# IO.net
KiCad netlist of a schematic drawn in Altium Designer
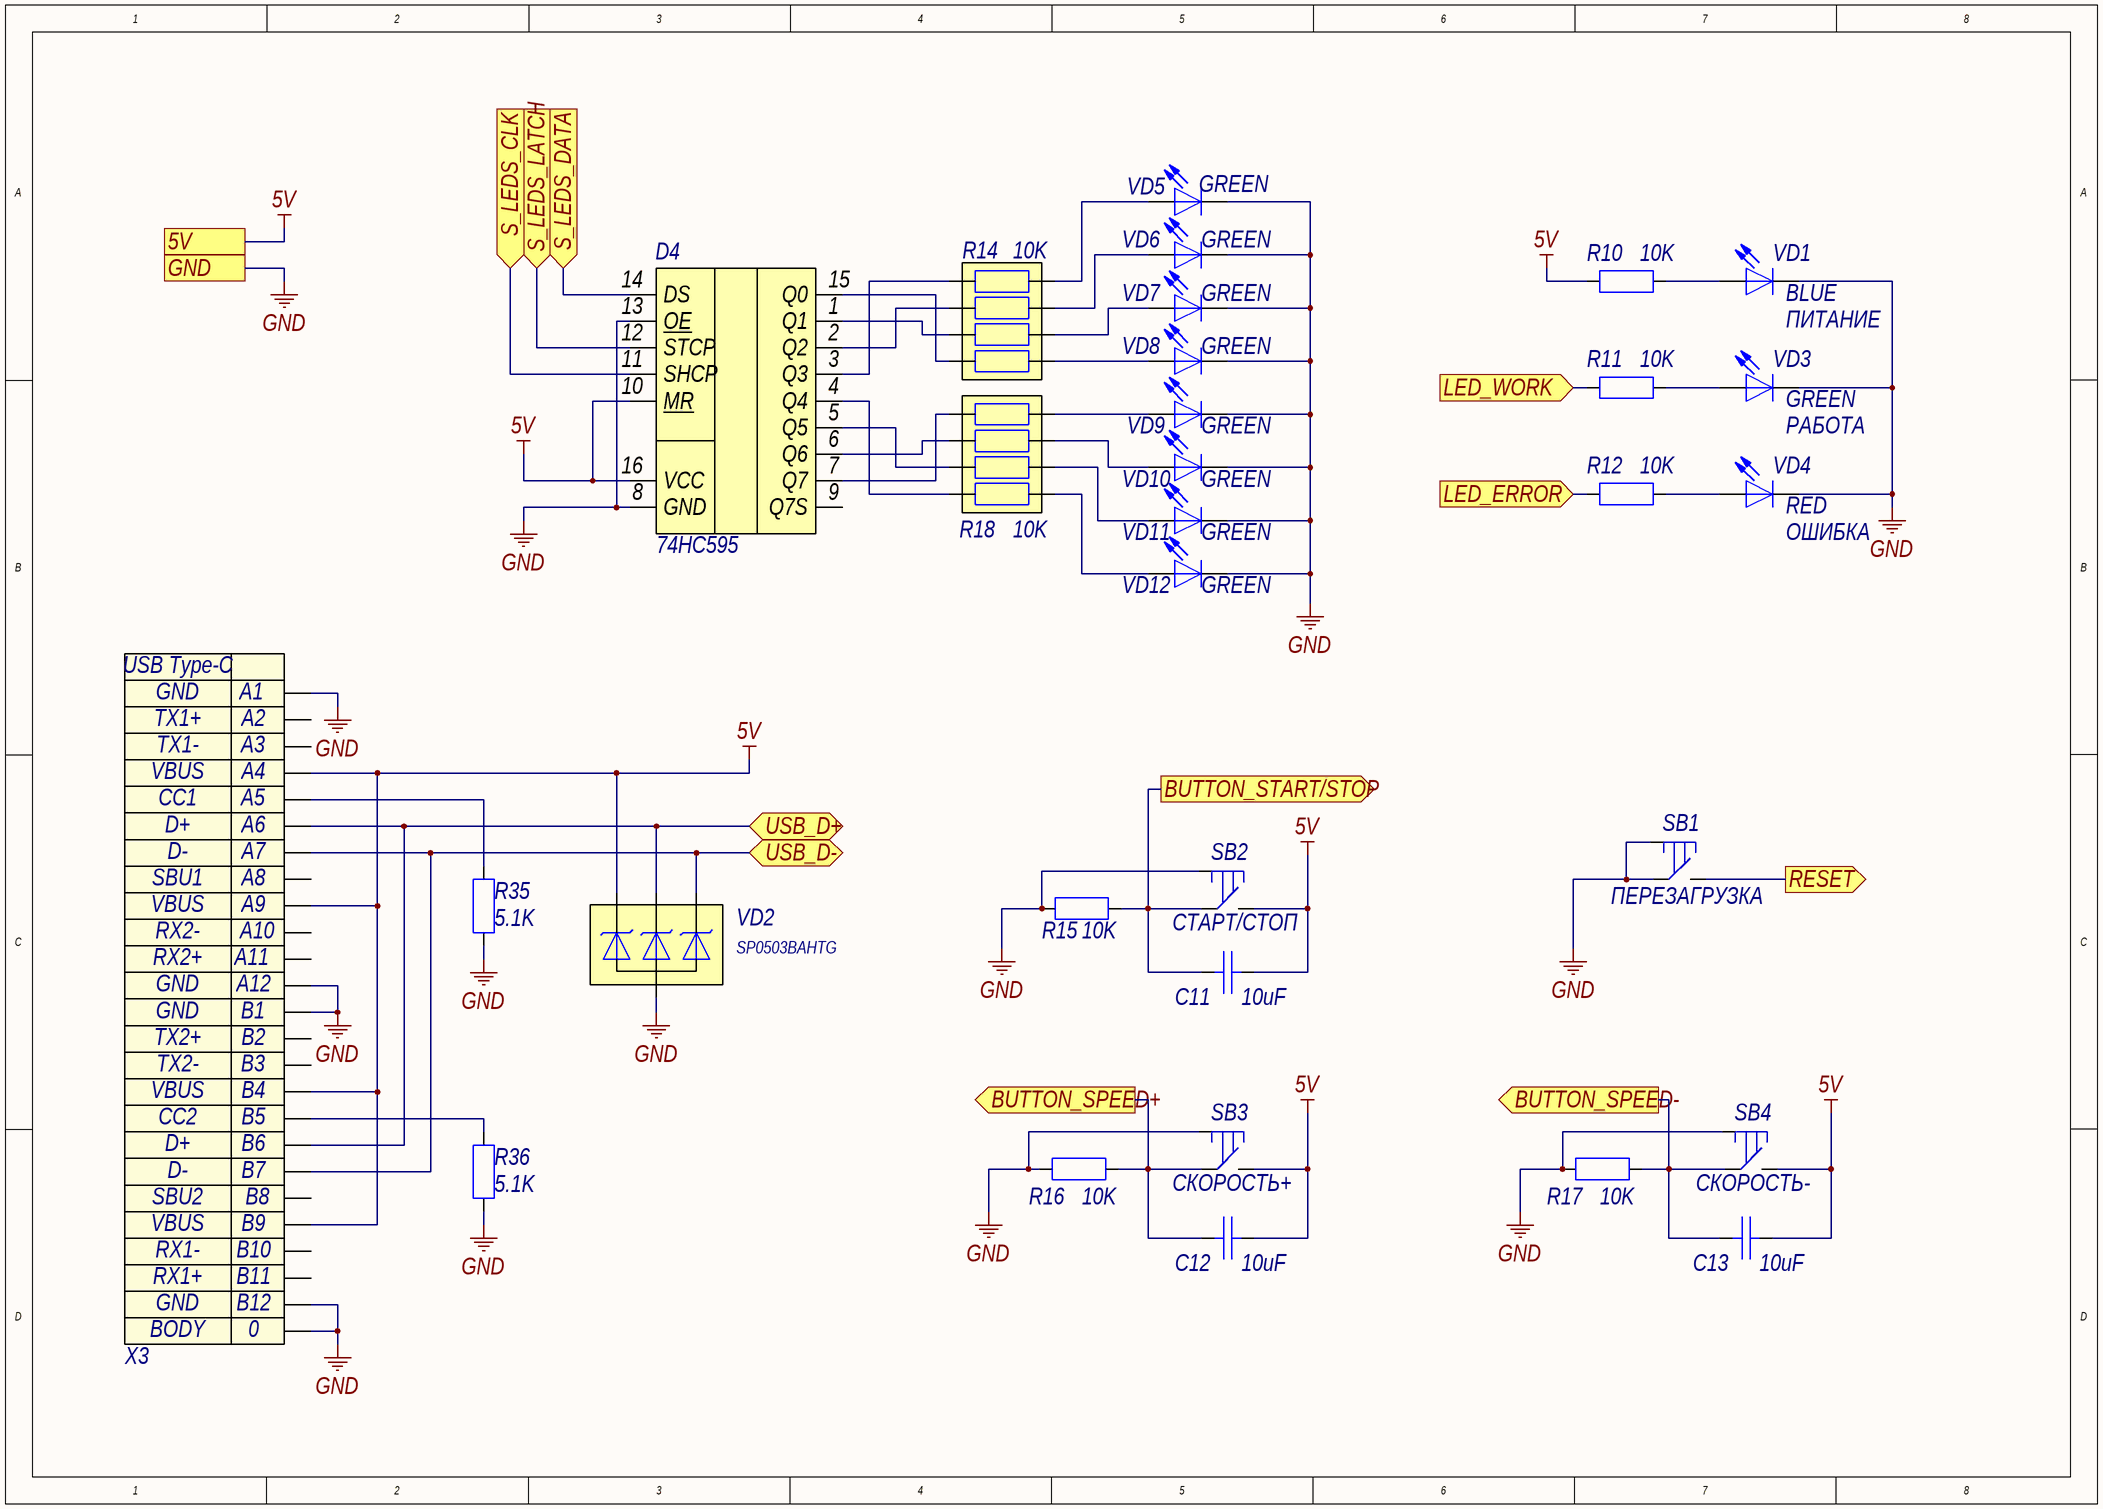
[diagram p0: IO.SchDoc]

(export (version "E")
  (design (tool "Eeschema 10.0.6"))
  (components
    (comp (ref "C11")
      (value "10uF")
      (footprint "Footprints:NPC0805")
      (description "Nonpolarized Capacitor (Ceramic)")
      (libsource (lib "Passive") (part "Nonpolarized Capacitor"))
    )
    (comp (ref "C12")
      (value "10uF")
      (footprint "Footprints:NPC0805")
      (description "Nonpolarized Capacitor (Ceramic)")
      (libsource (lib "Passive") (part "Nonpolarized Capacitor"))
    )
    (comp (ref "C13")
      (value "10uF")
      (footprint "Footprints:NPC0805")
      (description "Nonpolarized Capacitor (Ceramic)")
      (libsource (lib "Passive") (part "Nonpolarized Capacitor"))
    )
    (comp (ref "D4")
      (value "74HC595")
      (footprint "SOIC16")
      (description "Сдвиговый регистр, 8 каналов")
      (libsource (lib "Miscellaneous") (part "74HC595"))
    )
    (comp (ref "R10")
      (value "10K")
      (footprint "Footprints:R0805")
      (description "Resistor")
      (libsource (lib "") (part "Resistor_1"))
    )
    (comp (ref "R11")
      (value "10K")
      (footprint "Footprints:R0805")
      (description "Resistor")
      (libsource (lib "") (part "Resistor_1"))
    )
    (comp (ref "R12")
      (value "10K")
      (footprint "Footprints:R0805")
      (description "Resistor")
      (libsource (lib "") (part "Resistor_1"))
    )
    (comp (ref "R14")
      (value "10K")
      (footprint "Footprints:CAT16")
      (description "Resistor Array")
      (libsource (lib "Passive") (part "Resistor Array"))
    )
    (comp (ref "R15")
      (value "10K")
      (footprint "Footprints:R0805")
      (description "Resistor")
      (libsource (lib "") (part "Resistor_1"))
    )
    (comp (ref "R16")
      (value "10K")
      (footprint "Footprints:R0805")
      (description "Resistor")
      (libsource (lib "") (part "Resistor_1"))
    )
    (comp (ref "R17")
      (value "10K")
      (footprint "Footprints:R0805")
      (description "Resistor")
      (libsource (lib "") (part "Resistor_1"))
    )
    (comp (ref "R18")
      (value "10K")
      (footprint "Footprints:CAT16")
      (description "Resistor Array")
      (libsource (lib "Passive") (part "Resistor Array"))
    )
    (comp (ref "R35")
      (value "5.1K")
      (footprint "Footprints:R0805")
      (description "Resistor")
      (libsource (lib "Passive") (part "Resistor"))
    )
    (comp (ref "R36")
      (value "5.1K")
      (footprint "Footprints:R0805")
      (description "Resistor")
      (libsource (lib "Passive") (part "Resistor"))
    )
    (comp (ref "SB1")
      (value "~")
      (footprint "1-1437565-6 WITH LABEL")
      (description "Кнопка без фиксации")
      (fields (field (name "FUNCTION") "ПЕРЕЗАГРУЗКА"))
      (libsource (lib "LibSCH") (part "Button_SMD"))
    )
    (comp (ref "SB2")
      (value "~")
      (footprint "1-1437565-6 WITH LABEL")
      (description "Кнопка без фиксации")
      (fields (field (name "FUNCTION") "СТАРТ/СТОП"))
      (libsource (lib "LibSCH") (part "Button_SMD"))
    )
    (comp (ref "SB3")
      (value "~")
      (footprint "1-1437565-6 WITH LABEL")
      (description "Кнопка без фиксации")
      (fields (field (name "FUNCTION") "СКОРОСТЬ+"))
      (libsource (lib "LibSCH") (part "Button_SMD"))
    )
    (comp (ref "SB4")
      (value "~")
      (footprint "1-1437565-6 WITH LABEL")
      (description "Кнопка без фиксации")
      (fields (field (name "FUNCTION") "СКОРОСТЬ-"))
      (libsource (lib "LibSCH") (part "Button_SMD"))
    )
    (comp (ref "VD1")
      (value "~")
      (footprint "0805_LED _BLUE")
      (description "Светодиод SMD")
      (fields
        (field (name "NAME") "ПИТАНИЕ")
        (field (name "MANUFACTURER") "KGB")
        (field (name "COLOR") "BLUE")
      )
      (libsource (lib "Diodes") (part "LED"))
    )
    (comp (ref "VD2")
      (value "SP0503BAHTG")
      (footprint "Footprints:SOT143")
      (description "3 TVS Diodes assembly, 5V")
      (libsource (lib "Diodes") (part "SP0503BAHTG"))
    )
    (comp (ref "VD3")
      (value "~")
      (footprint "0805_LED _GREEN")
      (description "Светодиод SMD")
      (fields
        (field (name "NAME") "РАБОТА")
        (field (name "MANUFACTURER") "KGB")
        (field (name "COLOR") "GREEN")
      )
      (libsource (lib "Diodes") (part "LED"))
    )
    (comp (ref "VD4")
      (value "~")
      (footprint "0805_LED _RED")
      (description "Светодиод SMD")
      (fields (field (name "NAME") "ОШИБКА") (field (name "MANUFACTURER") "KGB") (field (name "COLOR") "RED"))
      (libsource (lib "Diodes") (part "LED"))
    )
    (comp (ref "VD5")
      (value "GREEN")
      (footprint "0805_LED _GREEN")
      (description "Светодиод SMD")
      (fields (field (name "MANUFACTURER") "KGB"))
      (libsource (lib "Diodes") (part "LED"))
    )
    (comp (ref "VD6")
      (value "~")
      (footprint "0805_LED _GREEN")
      (description "Светодиод SMD")
      (fields (field (name "MANUFACTURER") "KGB") (field (name "COLOR") "GREEN"))
      (libsource (lib "Diodes") (part "LED"))
    )
    (comp (ref "VD7")
      (value "~")
      (footprint "0805_LED _GREEN")
      (description "Светодиод SMD")
      (fields (field (name "MANUFACTURER") "KGB") (field (name "COLOR") "GREEN"))
      (libsource (lib "Diodes") (part "LED"))
    )
    (comp (ref "VD8")
      (value "~")
      (footprint "0805_LED _GREEN")
      (description "Светодиод SMD")
      (fields (field (name "MANUFACTURER") "KGB") (field (name "COLOR") "GREEN"))
      (libsource (lib "Diodes") (part "LED"))
    )
    (comp (ref "VD9")
      (value "~")
      (footprint "0805_LED _GREEN")
      (description "Светодиод SMD")
      (fields (field (name "MANUFACTURER") "KGB") (field (name "COLOR") "GREEN"))
      (libsource (lib "Diodes") (part "LED"))
    )
    (comp (ref "VD10")
      (value "~")
      (footprint "0805_LED _GREEN")
      (description "Светодиод SMD")
      (fields (field (name "MANUFACTURER") "KGB") (field (name "COLOR") "GREEN"))
      (libsource (lib "Diodes") (part "LED"))
    )
    (comp (ref "VD11")
      (value "~")
      (footprint "0805_LED _GREEN")
      (description "Светодиод SMD")
      (fields (field (name "MANUFACTURER") "KGB") (field (name "COLOR") "GREEN"))
      (libsource (lib "Diodes") (part "LED"))
    )
    (comp (ref "VD12")
      (value "~")
      (footprint "0805_LED _GREEN")
      (description "Светодиод SMD")
      (fields (field (name "MANUFACTURER") "KGB") (field (name "COLOR") "GREEN"))
      (libsource (lib "Diodes") (part "LED"))
    )
    (comp (ref "X3")
      (value "USB Type-C")
      (footprint "Footprints:USB Type-C Vertical")
      (description "USB Type-C connector")
      (libsource (lib "Mechanical") (part "USB Type-C"))
    )
  )
  (nets
    (net (code "1") (name "/BUTTON_SPEED+") (class "Default")
      (node (ref "C12") (pin "1") (pinfunction "1_1") (pintype "passive"))
      (node (ref "R16") (pin "2") (pinfunction "2_2") (pintype "passive"))
      (node (ref "SB3") (pin "1") (pinfunction "1_1") (pintype "passive"))
    )
    (net (code "2") (name "/BUTTON_SPEED-") (class "Default")
      (node (ref "C13") (pin "1") (pinfunction "1_1") (pintype "passive"))
      (node (ref "R17") (pin "2") (pinfunction "2_2") (pintype "passive"))
      (node (ref "SB4") (pin "1") (pinfunction "1_1") (pintype "passive"))
    )
    (net (code "3") (name "/BUTTON_START{slash}STOP") (class "Default")
      (node (ref "C11") (pin "1") (pinfunction "1_1") (pintype "passive"))
      (node (ref "R15") (pin "2") (pinfunction "2_2") (pintype "passive"))
      (node (ref "SB2") (pin "1") (pinfunction "1_1") (pintype "passive"))
    )
    (net (code "4") (name "/LED_ERROR") (class "Default")
      (node (ref "R12") (pin "1") (pinfunction "1_1") (pintype "passive"))
    )
    (net (code "5") (name "/LED_WORK") (class "Default")
      (node (ref "R11") (pin "1") (pinfunction "1_1") (pintype "passive"))
    )
    (net (code "6") (name "/RESET") (class "Default")
      (node (ref "SB1") (pin "2") (pinfunction "2_2") (pintype "passive"))
    )
    (net (code "7") (name "/S_LEDS_CLK") (class "Default")
      (node (ref "D4") (pin "11") (pinfunction "SHCP_11") (pintype "passive"))
    )
    (net (code "8") (name "/S_LEDS_DATA") (class "Default")
      (node (ref "D4") (pin "14") (pinfunction "DS_14") (pintype "passive"))
    )
    (net (code "9") (name "/S_LEDS_LATCH") (class "Default")
      (node (ref "D4") (pin "12") (pinfunction "STCP_12") (pintype "passive"))
    )
    (net (code "10") (name "/USB_D+") (class "Default")
      (node (ref "VD2") (pin "3") (pinfunction "C_3") (pintype "passive"))
      (node (ref "X3") (pin "A6") (pintype "passive"))
      (node (ref "X3") (pin "B6") (pintype "passive"))
    )
    (net (code "11") (name "/USB_D-") (class "Default")
      (node (ref "VD2") (pin "4") (pinfunction "C_4") (pintype "passive"))
      (node (ref "X3") (pin "A7") (pintype "passive"))
      (node (ref "X3") (pin "B7") (pintype "passive"))
    )
    (net (code "12") (name "5V") (class "Default")
      (node (ref "C11") (pin "2") (pinfunction "2_2") (pintype "passive"))
      (node (ref "C12") (pin "2") (pinfunction "2_2") (pintype "passive"))
      (node (ref "C13") (pin "2") (pinfunction "2_2") (pintype "passive"))
      (node (ref "D4") (pin "10") (pinfunction "MR_10") (pintype "passive"))
      (node (ref "D4") (pin "16") (pinfunction "VCC_16") (pintype "passive"))
      (node (ref "R10") (pin "1") (pinfunction "1_1") (pintype "passive"))
      (node (ref "SB2") (pin "2") (pinfunction "2_2") (pintype "passive"))
      (node (ref "SB3") (pin "2") (pinfunction "2_2") (pintype "passive"))
      (node (ref "SB4") (pin "2") (pinfunction "2_2") (pintype "passive"))
      (node (ref "VD2") (pin "2") (pinfunction "C_2") (pintype "passive"))
      (node (ref "X3") (pin "A4") (pintype "passive"))
      (node (ref "X3") (pin "A9") (pintype "passive"))
      (node (ref "X3") (pin "B4") (pintype "passive"))
      (node (ref "X3") (pin "B9") (pintype "passive"))
    )
    (net (code "13") (name "GND") (class "Default")
      (node (ref "D4") (pin "13") (pinfunction "OE_13") (pintype "passive"))
      (node (ref "D4") (pin "8") (pinfunction "GND_8") (pintype "passive"))
      (node (ref "R15") (pin "1") (pinfunction "1_1") (pintype "passive"))
      (node (ref "R16") (pin "1") (pinfunction "1_1") (pintype "passive"))
      (node (ref "R17") (pin "1") (pinfunction "1_1") (pintype "passive"))
      (node (ref "R35") (pin "1") (pinfunction "1_1") (pintype "passive"))
      (node (ref "R36") (pin "1") (pinfunction "1_1") (pintype "passive"))
      (node (ref "SB1") (pin "1") (pinfunction "1_1") (pintype "passive"))
      (node (ref "SB1") (pin "3") (pinfunction "GND_3") (pintype "passive"))
      (node (ref "SB2") (pin "3") (pinfunction "GND_3") (pintype "passive"))
      (node (ref "SB3") (pin "3") (pinfunction "GND_3") (pintype "passive"))
      (node (ref "SB4") (pin "3") (pinfunction "GND_3") (pintype "passive"))
      (node (ref "VD1") (pin "1") (pinfunction "K_1") (pintype "passive"))
      (node (ref "VD10") (pin "1") (pinfunction "K_1") (pintype "passive"))
      (node (ref "VD11") (pin "1") (pinfunction "K_1") (pintype "passive"))
      (node (ref "VD12") (pin "1") (pinfunction "K_1") (pintype "passive"))
      (node (ref "VD2") (pin "1") (pinfunction "A_1") (pintype "passive"))
      (node (ref "VD3") (pin "1") (pinfunction "K_1") (pintype "passive"))
      (node (ref "VD4") (pin "1") (pinfunction "K_1") (pintype "passive"))
      (node (ref "VD5") (pin "1") (pinfunction "K_1") (pintype "passive"))
      (node (ref "VD6") (pin "1") (pinfunction "K_1") (pintype "passive"))
      (node (ref "VD7") (pin "1") (pinfunction "K_1") (pintype "passive"))
      (node (ref "VD8") (pin "1") (pinfunction "K_1") (pintype "passive"))
      (node (ref "VD9") (pin "1") (pinfunction "K_1") (pintype "passive"))
      (node (ref "X3") (pin "0") (pintype "passive"))
      (node (ref "X3") (pin "A1") (pintype "passive"))
      (node (ref "X3") (pin "A12") (pintype "passive"))
      (node (ref "X3") (pin "B1") (pintype "passive"))
      (node (ref "X3") (pin "B12") (pintype "passive"))
    )
    (net (code "14") (name "Net-(D4-Q0)") (class "Default")
      (node (ref "D4") (pin "15") (pinfunction "Q0_15") (pintype "passive"))
      (node (ref "R14") (pin "4") (pinfunction "4_4") (pintype "passive"))
    )
    (net (code "15") (name "Net-(D4-Q1)") (class "Default")
      (node (ref "D4") (pin "1") (pinfunction "Q1_1") (pintype "passive"))
      (node (ref "R14") (pin "3") (pinfunction "3_3") (pintype "passive"))
    )
    (net (code "16") (name "Net-(D4-Q2)") (class "Default")
      (node (ref "D4") (pin "2") (pinfunction "Q2_2") (pintype "passive"))
      (node (ref "R14") (pin "2") (pinfunction "2_2") (pintype "passive"))
    )
    (net (code "17") (name "Net-(D4-Q3)") (class "Default")
      (node (ref "D4") (pin "3") (pinfunction "Q3_3") (pintype "passive"))
      (node (ref "R14") (pin "1") (pinfunction "1_1") (pintype "passive"))
    )
    (net (code "18") (name "Net-(D4-Q4)") (class "Default")
      (node (ref "D4") (pin "4") (pinfunction "Q4_4") (pintype "passive"))
      (node (ref "R18") (pin "4") (pinfunction "4_4") (pintype "passive"))
    )
    (net (code "19") (name "Net-(D4-Q5)") (class "Default")
      (node (ref "D4") (pin "5") (pinfunction "Q5_5") (pintype "passive"))
      (node (ref "R18") (pin "3") (pinfunction "3_3") (pintype "passive"))
    )
    (net (code "20") (name "Net-(D4-Q6)") (class "Default")
      (node (ref "D4") (pin "6") (pinfunction "Q6_6") (pintype "passive"))
      (node (ref "R18") (pin "2") (pinfunction "2_2") (pintype "passive"))
    )
    (net (code "21") (name "Net-(D4-Q7)") (class "Default")
      (node (ref "D4") (pin "7") (pinfunction "Q7_7") (pintype "passive"))
      (node (ref "R18") (pin "1") (pinfunction "1_1") (pintype "passive"))
    )
    (net (code "22") (name "Net-(R35-Pad2)") (class "Default")
      (node (ref "R35") (pin "2") (pinfunction "2_2") (pintype "passive"))
      (node (ref "X3") (pin "A5") (pintype "passive"))
    )
    (net (code "23") (name "Net-(R36-Pad2)") (class "Default")
      (node (ref "R36") (pin "2") (pinfunction "2_2") (pintype "passive"))
      (node (ref "X3") (pin "B5") (pintype "passive"))
    )
    (net (code "24") (name "Net-(VD1-A)") (class "Default")
      (node (ref "R10") (pin "2") (pinfunction "2_2") (pintype "passive"))
      (node (ref "VD1") (pin "2") (pinfunction "A_2") (pintype "passive"))
    )
    (net (code "25") (name "Net-(VD3-A)") (class "Default")
      (node (ref "R11") (pin "2") (pinfunction "2_2") (pintype "passive"))
      (node (ref "VD3") (pin "2") (pinfunction "A_2") (pintype "passive"))
    )
    (net (code "26") (name "Net-(VD4-A)") (class "Default")
      (node (ref "R12") (pin "2") (pinfunction "2_2") (pintype "passive"))
      (node (ref "VD4") (pin "2") (pinfunction "A_2") (pintype "passive"))
    )
    (net (code "27") (name "Net-(VD5-A)") (class "Default")
      (node (ref "R14") (pin "8") (pinfunction "8_8") (pintype "passive"))
      (node (ref "VD5") (pin "2") (pinfunction "A_2") (pintype "passive"))
    )
    (net (code "28") (name "Net-(VD6-A)") (class "Default")
      (node (ref "R14") (pin "7") (pinfunction "7_7") (pintype "passive"))
      (node (ref "VD6") (pin "2") (pinfunction "A_2") (pintype "passive"))
    )
    (net (code "29") (name "Net-(VD7-A)") (class "Default")
      (node (ref "R14") (pin "6") (pinfunction "6_6") (pintype "passive"))
      (node (ref "VD7") (pin "2") (pinfunction "A_2") (pintype "passive"))
    )
    (net (code "30") (name "Net-(VD8-A)") (class "Default")
      (node (ref "R14") (pin "5") (pinfunction "5_5") (pintype "passive"))
      (node (ref "VD8") (pin "2") (pinfunction "A_2") (pintype "passive"))
    )
    (net (code "31") (name "Net-(VD9-A)") (class "Default")
      (node (ref "R18") (pin "8") (pinfunction "8_8") (pintype "passive"))
      (node (ref "VD9") (pin "2") (pinfunction "A_2") (pintype "passive"))
    )
    (net (code "32") (name "Net-(VD10-A)") (class "Default")
      (node (ref "R18") (pin "7") (pinfunction "7_7") (pintype "passive"))
      (node (ref "VD10") (pin "2") (pinfunction "A_2") (pintype "passive"))
    )
    (net (code "33") (name "Net-(VD11-A)") (class "Default")
      (node (ref "R18") (pin "6") (pinfunction "6_6") (pintype "passive"))
      (node (ref "VD11") (pin "2") (pinfunction "A_2") (pintype "passive"))
    )
    (net (code "34") (name "Net-(VD12-A)") (class "Default")
      (node (ref "R18") (pin "5") (pinfunction "5_5") (pintype "passive"))
      (node (ref "VD12") (pin "2") (pinfunction "A_2") (pintype "passive"))
    )
    (net (code "35") (name "unconnected-(D4-Q7S-Pad9)") (class "Default")
      (node (ref "D4") (pin "9") (pinfunction "Q7S_9") (pintype "passive"))
    )
    (net (code "36") (name "unconnected-(X3-PadA2)") (class "Default")
      (node (ref "X3") (pin "A2") (pintype "passive"))
    )
    (net (code "37") (name "unconnected-(X3-PadA3)") (class "Default")
      (node (ref "X3") (pin "A3") (pintype "passive"))
    )
    (net (code "38") (name "unconnected-(X3-PadA8)") (class "Default")
      (node (ref "X3") (pin "A8") (pintype "passive"))
    )
    (net (code "39") (name "unconnected-(X3-PadA10)") (class "Default")
      (node (ref "X3") (pin "A10") (pintype "passive"))
    )
    (net (code "40") (name "unconnected-(X3-PadA11)") (class "Default")
      (node (ref "X3") (pin "A11") (pintype "passive"))
    )
    (net (code "41") (name "unconnected-(X3-PadB2)") (class "Default")
      (node (ref "X3") (pin "B2") (pintype "passive"))
    )
    (net (code "42") (name "unconnected-(X3-PadB3)") (class "Default")
      (node (ref "X3") (pin "B3") (pintype "passive"))
    )
    (net (code "43") (name "unconnected-(X3-PadB8)") (class "Default")
      (node (ref "X3") (pin "B8") (pintype "passive"))
    )
    (net (code "44") (name "unconnected-(X3-PadB10)") (class "Default")
      (node (ref "X3") (pin "B10") (pintype "passive"))
    )
    (net (code "45") (name "unconnected-(X3-PadB11)") (class "Default")
      (node (ref "X3") (pin "B11") (pintype "passive"))
    )
  )
)
